# coreboards_mod001_rp2040_v01.net
KiCad netlist of a schematic drawn in EasyEDA Pro
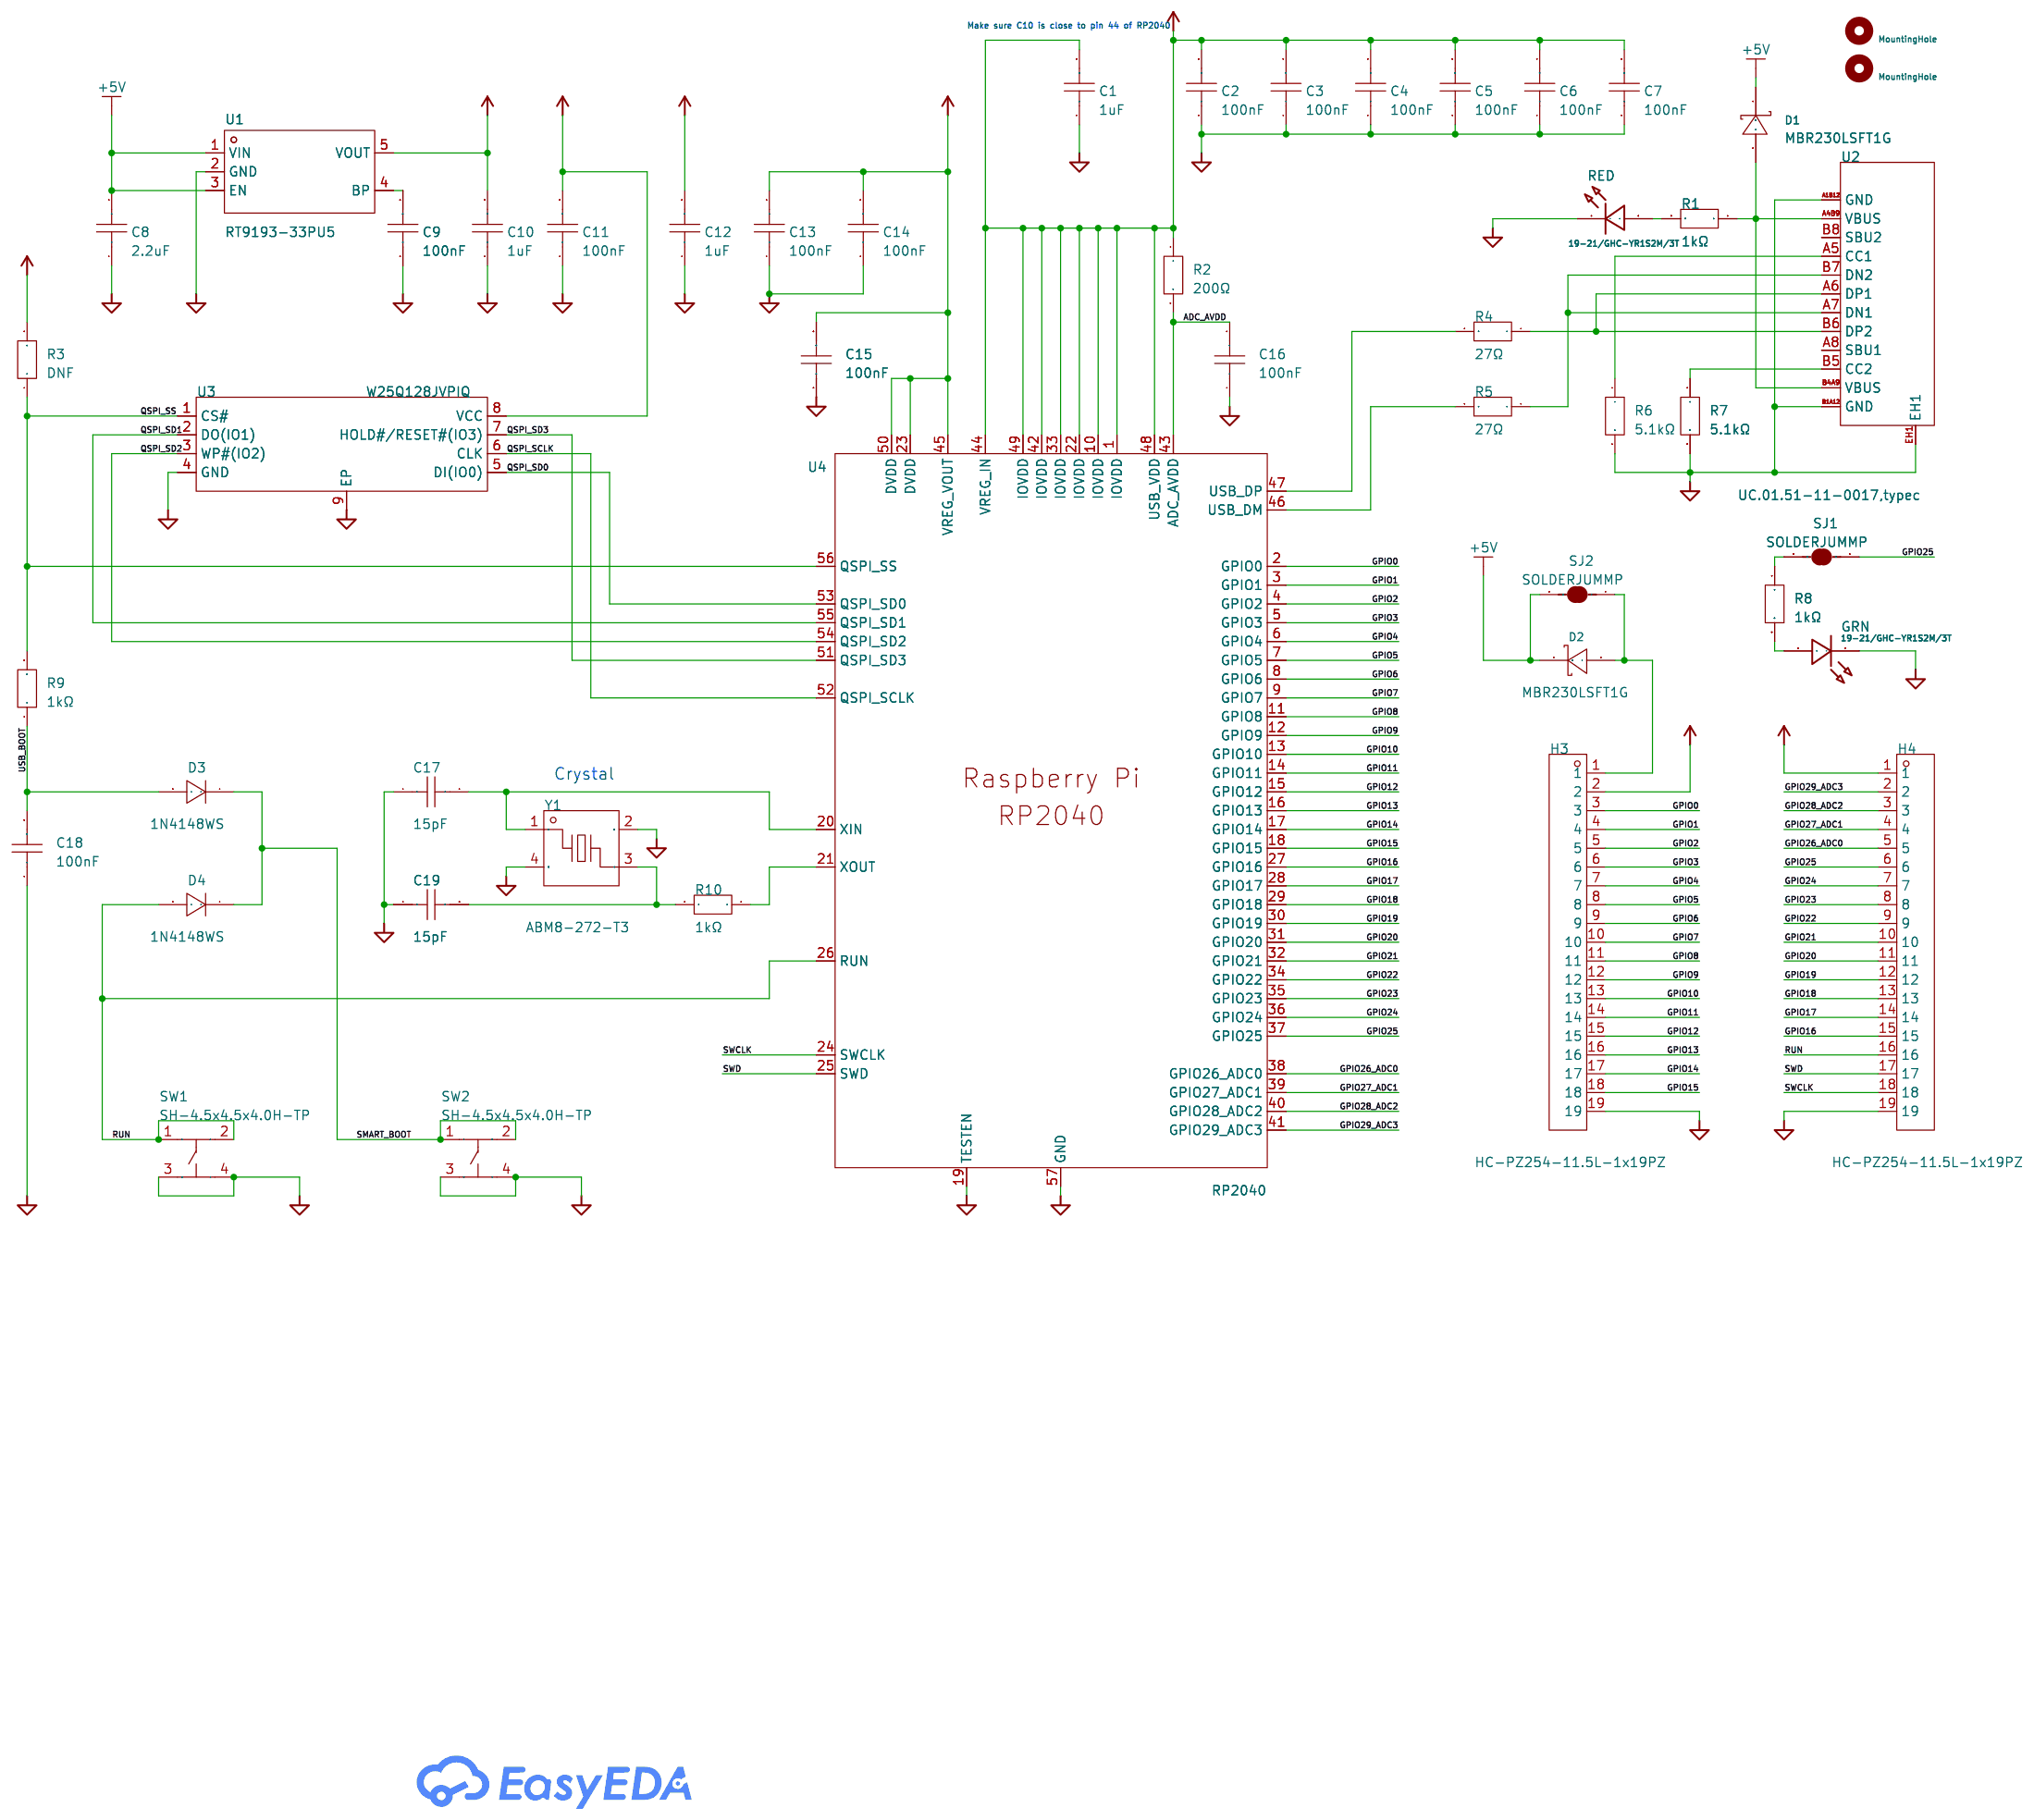
[diagram p0: schematic sheet]

(export (version "E")
  (design (tool "Eeschema 10.0.6"))
  (components
    (comp (ref "C1")
      (value "1uF")
      (footprint "easyedapro:C0603")
      (description "Capacitance:1nF Tolerance:±5% Tolerance:±5% Voltage Rating:200V Temperature Coefficient:C0G")
      (fields
        (field (name "Manufacturer Part") "C0603C102J2GECAUTO")
        (field (name "Manufacturer") "KEMET(基美)")
      )
      (libsource (lib "easyedapro") (part "C0603C102J2GECAUTO"))
    )
    (comp (ref "C2")
      (value "100nF")
      (footprint "easyedapro:C0603")
      (description "Capacitance:1nF Tolerance:±5% Tolerance:±5% Voltage Rating:200V Temperature Coefficient:C0G")
      (fields
        (field (name "Manufacturer Part") "C0603C102J2GECAUTO")
        (field (name "Manufacturer") "KEMET(基美)")
      )
      (libsource (lib "easyedapro") (part "C0603C102J2GECAUTO"))
    )
    (comp (ref "C3")
      (value "100nF")
      (footprint "easyedapro:C0603")
      (description "Capacitance:1nF Tolerance:±5% Tolerance:±5% Voltage Rating:200V Temperature Coefficient:C0G")
      (fields
        (field (name "Manufacturer Part") "C0603C102J2GECAUTO")
        (field (name "Manufacturer") "KEMET(基美)")
      )
      (libsource (lib "easyedapro") (part "C0603C102J2GECAUTO"))
    )
    (comp (ref "C4")
      (value "100nF")
      (footprint "easyedapro:C0603")
      (description "Capacitance:1nF Tolerance:±5% Tolerance:±5% Voltage Rating:200V Temperature Coefficient:C0G")
      (fields
        (field (name "Manufacturer Part") "C0603C102J2GECAUTO")
        (field (name "Manufacturer") "KEMET(基美)")
      )
      (libsource (lib "easyedapro") (part "C0603C102J2GECAUTO"))
    )
    (comp (ref "C5")
      (value "100nF")
      (footprint "easyedapro:C0603")
      (description "Capacitance:1nF Tolerance:±5% Tolerance:±5% Voltage Rating:200V Temperature Coefficient:C0G")
      (fields
        (field (name "Manufacturer Part") "C0603C102J2GECAUTO")
        (field (name "Manufacturer") "KEMET(基美)")
      )
      (libsource (lib "easyedapro") (part "C0603C102J2GECAUTO"))
    )
    (comp (ref "C6")
      (value "100nF")
      (footprint "easyedapro:C0603")
      (description "Capacitance:1nF Tolerance:±5% Tolerance:±5% Voltage Rating:200V Temperature Coefficient:C0G")
      (fields
        (field (name "Manufacturer Part") "C0603C102J2GECAUTO")
        (field (name "Manufacturer") "KEMET(基美)")
      )
      (libsource (lib "easyedapro") (part "C0603C102J2GECAUTO"))
    )
    (comp (ref "C7")
      (value "100nF")
      (footprint "easyedapro:C0603")
      (description "Capacitance:1nF Tolerance:±5% Tolerance:±5% Voltage Rating:200V Temperature Coefficient:C0G")
      (fields
        (field (name "Manufacturer Part") "C0603C102J2GECAUTO")
        (field (name "Manufacturer") "KEMET(基美)")
      )
      (libsource (lib "easyedapro") (part "C0603C102J2GECAUTO"))
    )
    (comp (ref "C8")
      (value "2.2uF")
      (footprint "easyedapro:C0603")
      (description "Capacitance:1nF Tolerance:±5% Tolerance:±5% Voltage Rating:200V Temperature Coefficient:C0G")
      (fields
        (field (name "Manufacturer Part") "C0603C102J2GECAUTO")
        (field (name "Manufacturer") "KEMET(基美)")
      )
      (libsource (lib "easyedapro") (part "C0603C102J2GECAUTO"))
    )
    (comp (ref "C9")
      (value "100nF")
      (footprint "easyedapro:C0603")
      (description "Capacitance:1nF Tolerance:±5% Tolerance:±5% Voltage Rating:200V Temperature Coefficient:C0G")
      (fields
        (field (name "Manufacturer Part") "C0603C102J2GECAUTO")
        (field (name "Manufacturer") "KEMET(基美)")
      )
      (libsource (lib "easyedapro") (part "C0603C102J2GECAUTO"))
    )
    (comp (ref "C10")
      (value "1uF")
      (footprint "easyedapro:C0603")
      (description "Capacitance:1nF Tolerance:±5% Tolerance:±5% Voltage Rating:200V Temperature Coefficient:C0G")
      (fields
        (field (name "Manufacturer Part") "C0603C102J2GECAUTO")
        (field (name "Manufacturer") "KEMET(基美)")
      )
      (libsource (lib "easyedapro") (part "C0603C102J2GECAUTO"))
    )
    (comp (ref "C11")
      (value "100nF")
      (footprint "easyedapro:C0603")
      (description "Capacitance:1nF Tolerance:±5% Tolerance:±5% Voltage Rating:200V Temperature Coefficient:C0G")
      (fields
        (field (name "Manufacturer Part") "C0603C102J2GECAUTO")
        (field (name "Manufacturer") "KEMET(基美)")
      )
      (libsource (lib "easyedapro") (part "C0603C102J2GECAUTO"))
    )
    (comp (ref "C12")
      (value "1uF")
      (footprint "easyedapro:C0603")
      (description "Capacitance:1nF Tolerance:±5% Tolerance:±5% Voltage Rating:200V Temperature Coefficient:C0G")
      (fields
        (field (name "Manufacturer Part") "C0603C102J2GECAUTO")
        (field (name "Manufacturer") "KEMET(基美)")
      )
      (libsource (lib "easyedapro") (part "C0603C102J2GECAUTO"))
    )
    (comp (ref "C13")
      (value "100nF")
      (footprint "easyedapro:C0603")
      (description "Capacitance:1nF Tolerance:±5% Tolerance:±5% Voltage Rating:200V Temperature Coefficient:C0G")
      (fields
        (field (name "Manufacturer Part") "C0603C102J2GECAUTO")
        (field (name "Manufacturer") "KEMET(基美)")
      )
      (libsource (lib "easyedapro") (part "C0603C102J2GECAUTO"))
    )
    (comp (ref "C14")
      (value "100nF")
      (footprint "easyedapro:C0603")
      (description "Capacitance:1nF Tolerance:±5% Tolerance:±5% Voltage Rating:200V Temperature Coefficient:C0G")
      (fields
        (field (name "Manufacturer Part") "C0603C102J2GECAUTO")
        (field (name "Manufacturer") "KEMET(基美)")
      )
      (libsource (lib "easyedapro") (part "C0603C102J2GECAUTO"))
    )
    (comp (ref "C15")
      (value "100nF")
      (footprint "easyedapro:C0603")
      (description "Capacitance:1nF Tolerance:±5% Tolerance:±5% Voltage Rating:200V Temperature Coefficient:C0G")
      (fields
        (field (name "Manufacturer Part") "C0603C102J2GECAUTO")
        (field (name "Manufacturer") "KEMET(基美)")
      )
      (libsource (lib "easyedapro") (part "C0603C102J2GECAUTO"))
    )
    (comp (ref "C16")
      (value "100nF")
      (footprint "easyedapro:C0603")
      (description "Capacitance:1nF Tolerance:±5% Tolerance:±5% Voltage Rating:200V Temperature Coefficient:C0G")
      (fields
        (field (name "Manufacturer Part") "C0603C102J2GECAUTO")
        (field (name "Manufacturer") "KEMET(基美)")
      )
      (libsource (lib "easyedapro") (part "C0603C102J2GECAUTO"))
    )
    (comp (ref "C17")
      (value "15pF")
      (footprint "easyedapro:C0603")
      (description "Capacitance:1nF Tolerance:±5% Tolerance:±5% Voltage Rating:200V Temperature Coefficient:C0G")
      (fields
        (field (name "Manufacturer Part") "C0603C102J2GECAUTO")
        (field (name "Manufacturer") "KEMET(基美)")
      )
      (libsource (lib "easyedapro") (part "C0603C102J2GECAUTO"))
    )
    (comp (ref "C18")
      (value "100nF")
      (footprint "easyedapro:C0603")
      (description "Capacitance:1nF Tolerance:±5% Tolerance:±5% Voltage Rating:200V Temperature Coefficient:C0G")
      (fields
        (field (name "Manufacturer Part") "C0603C102J2GECAUTO")
        (field (name "Manufacturer") "KEMET(基美)")
      )
      (libsource (lib "easyedapro") (part "C0603C102J2GECAUTO"))
    )
    (comp (ref "C19")
      (value "15pF")
      (footprint "easyedapro:C0603")
      (description "Capacitance:1nF Tolerance:±5% Tolerance:±5% Voltage Rating:200V Temperature Coefficient:C0G")
      (fields
        (field (name "Manufacturer Part") "C0603C102J2GECAUTO")
        (field (name "Manufacturer") "KEMET(基美)")
      )
      (libsource (lib "easyedapro") (part "C0603C102J2GECAUTO"))
    )
    (comp (ref "D1")
      (value "MBR230LSFT1G")
      (footprint "easyedapro:SOD-123FL_L2.7-W1.8-LS3.8-RD")
      (fields (field (name "Manufacturer") "onsemi(安森美)"))
      (libsource (lib "easyedapro") (part "MBR230LSFT1G"))
    )
    (comp (ref "D2")
      (value "MBR230LSFT1G")
      (footprint "easyedapro:SOD-123FL_L2.7-W1.8-LS3.8-RD")
      (fields (field (name "Manufacturer") "onsemi(安森美)"))
      (libsource (lib "easyedapro") (part "MBR230LSFT1G"))
    )
    (comp (ref "D3")
      (value "1N4148WS")
      (footprint "easyedapro:SOD-323_L1.8-W1.3-LS2.5-RD")
      (fields (field (name "Manufacturer") "CJ(江苏长电/长晶)"))
      (libsource (lib "easyedapro") (part "1N4148WS T4"))
    )
    (comp (ref "D4")
      (value "1N4148WS")
      (footprint "easyedapro:SOD-323_L1.8-W1.3-LS2.5-RD")
      (fields (field (name "Manufacturer") "CJ(江苏长电/长晶)"))
      (libsource (lib "easyedapro") (part "1N4148WS T4"))
    )
    (comp (ref "GRN")
      (value "19-21/GHC-YR1S2M/3T")
      (footprint "easyedapro:LED-SMD_L1.6-W0.8-RD")
      (fields (field (name "Manufacturer") "EVERLIGHT(亿光)") (field (name "Contributor") "LCSC"))
      (libsource (lib "easyedapro") (part "19-21/GHC-YR1S2M/3T"))
    )
    (comp (ref "H1")
      (value "MountingHole")
      (footprint "easyedapro:MountingHole:MountingHole_2.7mm_M2.5")
      (libsource (lib "easyedapro") (part "Mechanical_MountingHole"))
    )
    (comp (ref "H2")
      (value "MountingHole")
      (footprint "easyedapro:MountingHole:MountingHole_2.7mm_M2.5")
      (libsource (lib "easyedapro") (part "Mechanical_MountingHole"))
    )
    (comp (ref "H3")
      (value "HC-PZ254-11.5L-1x19PZ")
      (footprint "easyedapro:HDR-TH_19P-P2.54-V-M")
      (fields (field (name "Manufacturer") "HC(虹成电子)"))
      (libsource (lib "easyedapro") (part "HC-PZ254-11.5L-1X19PZ"))
    )
    (comp (ref "H4")
      (value "HC-PZ254-11.5L-1x19PZ")
      (footprint "easyedapro:HDR-TH_19P-P2.54-V-M")
      (fields (field (name "Manufacturer") "HC(虹成电子)"))
      (libsource (lib "easyedapro") (part "HC-PZ254-11.5L-1X19PZ"))
    )
    (comp (ref "R1")
      (value "1kΩ")
      (footprint "easyedapro:R0603")
      (fields (field (name "Manufacturer Part") "RCC06031K50FKEA") (field (name "Manufacturer") "VISHAY(威世)"))
      (libsource (lib "easyedapro") (part "RCC06031K50FKEA"))
    )
    (comp (ref "R2")
      (value "200Ω")
      (footprint "easyedapro:R0603")
      (fields (field (name "Manufacturer Part") "RCC06031K50FKEA") (field (name "Manufacturer") "VISHAY(威世)"))
      (libsource (lib "easyedapro") (part "RCC06031K50FKEA"))
    )
    (comp (ref "R3")
      (value "DNF")
      (footprint "easyedapro:R0603")
      (fields (field (name "Manufacturer Part") "RCC06031K50FKEA") (field (name "Manufacturer") "VISHAY(威世)"))
      (libsource (lib "easyedapro") (part "RCC06031K50FKEA"))
    )
    (comp (ref "R4")
      (value "27Ω")
      (footprint "easyedapro:R0603")
      (fields (field (name "Manufacturer Part") "RCC06031K50FKEA") (field (name "Manufacturer") "VISHAY(威世)"))
      (libsource (lib "easyedapro") (part "RCC06031K50FKEA"))
    )
    (comp (ref "R5")
      (value "27Ω")
      (footprint "easyedapro:R0603")
      (fields (field (name "Manufacturer Part") "RCC06031K50FKEA") (field (name "Manufacturer") "VISHAY(威世)"))
      (libsource (lib "easyedapro") (part "RCC06031K50FKEA"))
    )
    (comp (ref "R6")
      (value "5.1kΩ")
      (footprint "easyedapro:R0603")
      (fields (field (name "Manufacturer Part") "RCC06031K50FKEA") (field (name "Manufacturer") "VISHAY(威世)"))
      (libsource (lib "easyedapro") (part "RCC06031K50FKEA"))
    )
    (comp (ref "R7")
      (value "5.1kΩ")
      (footprint "easyedapro:R0603")
      (fields (field (name "Manufacturer Part") "RCC06031K50FKEA") (field (name "Manufacturer") "VISHAY(威世)"))
      (libsource (lib "easyedapro") (part "RCC06031K50FKEA"))
    )
    (comp (ref "R8")
      (value "1kΩ")
      (footprint "easyedapro:R0603")
      (fields (field (name "Manufacturer Part") "RCC06031K50FKEA") (field (name "Manufacturer") "VISHAY(威世)"))
      (libsource (lib "easyedapro") (part "RCC06031K50FKEA"))
    )
    (comp (ref "R9")
      (value "1kΩ")
      (footprint "easyedapro:R0603")
      (fields (field (name "Manufacturer Part") "RCC06031K50FKEA") (field (name "Manufacturer") "VISHAY(威世)"))
      (libsource (lib "easyedapro") (part "RCC06031K50FKEA"))
    )
    (comp (ref "R10")
      (value "1kΩ")
      (footprint "easyedapro:R0603")
      (fields (field (name "Manufacturer Part") "RCC06031K50FKEA") (field (name "Manufacturer") "VISHAY(威世)"))
      (libsource (lib "easyedapro") (part "RCC06031K50FKEA"))
    )
    (comp (ref "RED")
      (value "19-21/GHC-YR1S2M/3T")
      (footprint "easyedapro:LED-SMD_L1.6-W0.8-RD")
      (fields (field (name "Manufacturer") "EVERLIGHT(亿光)") (field (name "Contributor") "LCSC"))
      (libsource (lib "easyedapro") (part "19-21/GHC-YR1S2M/3T"))
    )
    (comp (ref "SJ1")
      (value "SOLDERJUMMP")
      (footprint "easyedapro:SJ_2S-NO")
      (fields (field (name "Contributor") "SparkFun"))
      (libsource (lib "easyedapro") (part "SOLDERJUMPERNO"))
    )
    (comp (ref "SJ2")
      (value "SOLDERJUMMP")
      (footprint "easyedapro:SJ_2S-NO")
      (fields (field (name "Contributor") "SparkFun"))
      (libsource (lib "easyedapro") (part "SOLDERJUMPERNO"))
    )
    (comp (ref "SW1")
      (value "SH-4.5x4.5x4.0H-TP")
      (footprint "easyedapro:SW-SMD_4P-SH-4.5X4.5X4.0H-TP")
      (fields (field (name "Manufacturer") "SHOU HAN(首韩)"))
      (libsource (lib "easyedapro") (part "SH-4.5X4.5X4.0H-TP"))
    )
    (comp (ref "SW2")
      (value "SH-4.5x4.5x4.0H-TP")
      (footprint "easyedapro:SW-SMD_4P-SH-4.5X4.5X4.0H-TP")
      (fields (field (name "Manufacturer") "SHOU HAN(首韩)"))
      (libsource (lib "easyedapro") (part "SH-4.5X4.5X4.0H-TP"))
    )
    (comp (ref "U1")
      (value "RT9193-33PU5")
      (footprint "easyedapro:SC-70-5_L2.0-W1.3-P0.65-LS2.1-BL")
      (description "Output Type:-")
      (libsource (lib "easyedapro") (part "RT9193-33PU5"))
    )
    (comp (ref "U2")
      (value "UC.01.51-11-0017,typec")
      (footprint "easyedapro:TYPE-C-SMD_UC.01.51-11-0017")
      (libsource (lib "easyedapro") (part "UC.01.51-11-0017,TYPEC"))
    )
    (comp (ref "U3")
      (value "W25Q128JVPIQ")
      (footprint "easyedapro:WSON-8_L5.0-W6.0-P1.27-BL-EP")
      (fields (field (name "Manufacturer") "Winbond(华邦)"))
      (libsource (lib "easyedapro") (part "W25Q128JVPIQ"))
    )
    (comp (ref "U4")
      (value "RP2040")
      (footprint "easyedapro:QFN-56_L7.0-W7.0-P0.40-TL-EP4.0")
      (fields (field (name "Manufacturer") "Raspberry Pi(树莓派)"))
      (libsource (lib "easyedapro") (part "RP2040_C2961140"))
    )
    (comp (ref "Y1")
      (value "ABM8-272-T3")
      (footprint "easyedapro:CRYSTAL-SMD_4P-L3.2-W2.5-BL-2")
      (libsource (lib "easyedapro") (part "ABM8-272-T3"))
    )
  )
  (nets
    (net (code "1") (name "+5V") (class "Default")
      (node (ref "C8") (pin "2") (pinfunction "2_2") (pintype "unspecified"))
      (node (ref "D1") (pin "1") (pinfunction "C_1") (pintype "input"))
      (node (ref "D2") (pin "1") (pinfunction "C_1") (pintype "input"))
      (node (ref "SJ2") (pin "2") (pinfunction "2_2") (pintype "unspecified"))
      (node (ref "U1") (pin "1") (pinfunction "VIN_1") (pintype "unspecified"))
      (node (ref "U1") (pin "3") (pinfunction "EN_3") (pintype "unspecified"))
    )
    (net (code "2") (name "/ADC_AVDD") (class "Default")
      (node (ref "C16") (pin "2") (pinfunction "2_2") (pintype "unspecified"))
      (node (ref "R2") (pin "2") (pinfunction "2_2") (pintype "unspecified"))
      (node (ref "U4") (pin "43") (pinfunction "ADC_AVDD_43") (pintype "bidirectional"))
    )
    (net (code "3") (name "/GPIO0") (class "Default")
      (node (ref "H3") (pin "3") (pinfunction "3_3") (pintype "unspecified"))
      (node (ref "U4") (pin "2") (pinfunction "GPIO0_2") (pintype "bidirectional"))
    )
    (net (code "4") (name "/GPIO1") (class "Default")
      (node (ref "H3") (pin "4") (pinfunction "4_4") (pintype "unspecified"))
      (node (ref "U4") (pin "3") (pinfunction "GPIO1_3") (pintype "bidirectional"))
    )
    (net (code "5") (name "/GPIO2") (class "Default")
      (node (ref "H3") (pin "5") (pinfunction "5_5") (pintype "unspecified"))
      (node (ref "U4") (pin "4") (pinfunction "GPIO2_4") (pintype "bidirectional"))
    )
    (net (code "6") (name "/GPIO3") (class "Default")
      (node (ref "H3") (pin "6") (pinfunction "6_6") (pintype "unspecified"))
      (node (ref "U4") (pin "5") (pinfunction "GPIO3_5") (pintype "bidirectional"))
    )
    (net (code "7") (name "/GPIO4") (class "Default")
      (node (ref "H3") (pin "7") (pinfunction "7_7") (pintype "unspecified"))
      (node (ref "U4") (pin "6") (pinfunction "GPIO4_6") (pintype "bidirectional"))
    )
    (net (code "8") (name "/GPIO5") (class "Default")
      (node (ref "H3") (pin "8") (pinfunction "8_8") (pintype "unspecified"))
      (node (ref "U4") (pin "7") (pinfunction "GPIO5_7") (pintype "bidirectional"))
    )
    (net (code "9") (name "/GPIO6") (class "Default")
      (node (ref "H3") (pin "9") (pinfunction "9_9") (pintype "unspecified"))
      (node (ref "U4") (pin "8") (pinfunction "GPIO6_8") (pintype "bidirectional"))
    )
    (net (code "10") (name "/GPIO7") (class "Default")
      (node (ref "H3") (pin "10") (pinfunction "10_10") (pintype "unspecified"))
      (node (ref "U4") (pin "9") (pinfunction "GPIO7_9") (pintype "bidirectional"))
    )
    (net (code "11") (name "/GPIO8") (class "Default")
      (node (ref "H3") (pin "11") (pinfunction "11_11") (pintype "unspecified"))
      (node (ref "U4") (pin "11") (pinfunction "GPIO8_11") (pintype "bidirectional"))
    )
    (net (code "12") (name "/GPIO9") (class "Default")
      (node (ref "H3") (pin "12") (pinfunction "12_12") (pintype "unspecified"))
      (node (ref "U4") (pin "12") (pinfunction "GPIO9_12") (pintype "bidirectional"))
    )
    (net (code "13") (name "/GPIO10") (class "Default")
      (node (ref "H3") (pin "13") (pinfunction "13_13") (pintype "unspecified"))
      (node (ref "U4") (pin "13") (pinfunction "GPIO10_13") (pintype "bidirectional"))
    )
    (net (code "14") (name "/GPIO11") (class "Default")
      (node (ref "H3") (pin "14") (pinfunction "14_14") (pintype "unspecified"))
      (node (ref "U4") (pin "14") (pinfunction "GPIO11_14") (pintype "bidirectional"))
    )
    (net (code "15") (name "/GPIO12") (class "Default")
      (node (ref "H3") (pin "15") (pinfunction "15_15") (pintype "unspecified"))
      (node (ref "U4") (pin "15") (pinfunction "GPIO12_15") (pintype "bidirectional"))
    )
    (net (code "16") (name "/GPIO13") (class "Default")
      (node (ref "H3") (pin "16") (pinfunction "16_16") (pintype "unspecified"))
      (node (ref "U4") (pin "16") (pinfunction "GPIO13_16") (pintype "bidirectional"))
    )
    (net (code "17") (name "/GPIO14") (class "Default")
      (node (ref "H3") (pin "17") (pinfunction "17_17") (pintype "unspecified"))
      (node (ref "U4") (pin "17") (pinfunction "GPIO14_17") (pintype "bidirectional"))
    )
    (net (code "18") (name "/GPIO15") (class "Default")
      (node (ref "H3") (pin "18") (pinfunction "18_18") (pintype "unspecified"))
      (node (ref "U4") (pin "18") (pinfunction "GPIO15_18") (pintype "bidirectional"))
    )
    (net (code "19") (name "/GPIO16") (class "Default")
      (node (ref "H4") (pin "15") (pinfunction "15_15") (pintype "unspecified"))
      (node (ref "U4") (pin "27") (pinfunction "GPIO16_27") (pintype "bidirectional"))
    )
    (net (code "20") (name "/GPIO17") (class "Default")
      (node (ref "H4") (pin "14") (pinfunction "14_14") (pintype "unspecified"))
      (node (ref "U4") (pin "28") (pinfunction "GPIO17_28") (pintype "bidirectional"))
    )
    (net (code "21") (name "/GPIO18") (class "Default")
      (node (ref "H4") (pin "13") (pinfunction "13_13") (pintype "unspecified"))
      (node (ref "U4") (pin "29") (pinfunction "GPIO18_29") (pintype "bidirectional"))
    )
    (net (code "22") (name "/GPIO19") (class "Default")
      (node (ref "H4") (pin "12") (pinfunction "12_12") (pintype "unspecified"))
      (node (ref "U4") (pin "30") (pinfunction "GPIO19_30") (pintype "bidirectional"))
    )
    (net (code "23") (name "/GPIO20") (class "Default")
      (node (ref "H4") (pin "11") (pinfunction "11_11") (pintype "unspecified"))
      (node (ref "U4") (pin "31") (pinfunction "GPIO20_31") (pintype "bidirectional"))
    )
    (net (code "24") (name "/GPIO21") (class "Default")
      (node (ref "H4") (pin "10") (pinfunction "10_10") (pintype "unspecified"))
      (node (ref "U4") (pin "32") (pinfunction "GPIO21_32") (pintype "bidirectional"))
    )
    (net (code "25") (name "/GPIO22") (class "Default")
      (node (ref "H4") (pin "9") (pinfunction "9_9") (pintype "unspecified"))
      (node (ref "U4") (pin "34") (pinfunction "GPIO22_34") (pintype "bidirectional"))
    )
    (net (code "26") (name "/GPIO23") (class "Default")
      (node (ref "H4") (pin "8") (pinfunction "8_8") (pintype "unspecified"))
      (node (ref "U4") (pin "35") (pinfunction "GPIO23_35") (pintype "bidirectional"))
    )
    (net (code "27") (name "/GPIO24") (class "Default")
      (node (ref "H4") (pin "7") (pinfunction "7_7") (pintype "unspecified"))
      (node (ref "U4") (pin "36") (pinfunction "GPIO24_36") (pintype "bidirectional"))
    )
    (net (code "28") (name "/GPIO25") (class "Default")
      (node (ref "H4") (pin "6") (pinfunction "6_6") (pintype "unspecified"))
      (node (ref "SJ1") (pin "1") (pinfunction "1_1") (pintype "unspecified"))
      (node (ref "U4") (pin "37") (pinfunction "GPIO25_37") (pintype "bidirectional"))
    )
    (net (code "29") (name "/GPIO26_ADC0") (class "Default")
      (node (ref "H4") (pin "5") (pinfunction "5_5") (pintype "unspecified"))
      (node (ref "U4") (pin "38") (pinfunction "GPIO26_ADC0_38") (pintype "bidirectional"))
    )
    (net (code "30") (name "/GPIO27_ADC1") (class "Default")
      (node (ref "H4") (pin "4") (pinfunction "4_4") (pintype "unspecified"))
      (node (ref "U4") (pin "39") (pinfunction "GPIO27_ADC1_39") (pintype "bidirectional"))
    )
    (net (code "31") (name "/GPIO28_ADC2") (class "Default")
      (node (ref "H4") (pin "3") (pinfunction "3_3") (pintype "unspecified"))
      (node (ref "U4") (pin "40") (pinfunction "GPIO28_ADC2_40") (pintype "bidirectional"))
    )
    (net (code "32") (name "/GPIO29_ADC3") (class "Default")
      (node (ref "H4") (pin "2") (pinfunction "2_2") (pintype "unspecified"))
      (node (ref "U4") (pin "41") (pinfunction "GPIO29_ADC3_41") (pintype "bidirectional"))
    )
    (net (code "33") (name "/QSPI_SCLK") (class "Default")
      (node (ref "U3") (pin "6") (pinfunction "CLK_6") (pintype "unspecified"))
      (node (ref "U4") (pin "52") (pinfunction "QSPI_SCLK_52") (pintype "output"))
    )
    (net (code "34") (name "/QSPI_SD0") (class "Default")
      (node (ref "U3") (pin "5") (pinfunction "DI(IO0)_5") (pintype "unspecified"))
      (node (ref "U4") (pin "53") (pinfunction "QSPI_SD0_53") (pintype "bidirectional"))
    )
    (net (code "35") (name "/QSPI_SD1") (class "Default")
      (node (ref "U3") (pin "2") (pinfunction "DO(IO1)_2") (pintype "unspecified"))
      (node (ref "U4") (pin "55") (pinfunction "QSPI_SD1_55") (pintype "bidirectional"))
    )
    (net (code "36") (name "/QSPI_SD2") (class "Default")
      (node (ref "U3") (pin "3") (pinfunction "WP#(IO2)_3") (pintype "unspecified"))
      (node (ref "U4") (pin "54") (pinfunction "QSPI_SD2_54") (pintype "bidirectional"))
    )
    (net (code "37") (name "/QSPI_SD3") (class "Default")
      (node (ref "U3") (pin "7") (pinfunction "HOLD#/RESET#(IO3)_7") (pintype "unspecified"))
      (node (ref "U4") (pin "51") (pinfunction "QSPI_SD3_51") (pintype "bidirectional"))
    )
    (net (code "38") (name "/QSPI_SS") (class "Default")
      (node (ref "R3") (pin "1") (pinfunction "1_1") (pintype "unspecified"))
      (node (ref "R9") (pin "2") (pinfunction "2_2") (pintype "unspecified"))
      (node (ref "U3") (pin "1") (pinfunction "CS#_1") (pintype "unspecified"))
      (node (ref "U4") (pin "56") (pinfunction "QSPI_SS_56") (pintype "bidirectional"))
    )
    (net (code "39") (name "/RUN") (class "Default")
      (node (ref "D4") (pin "2") (pinfunction "A_2") (pintype "unspecified"))
      (node (ref "H4") (pin "16") (pinfunction "16_16") (pintype "unspecified"))
      (node (ref "SW1") (pin "1") (pinfunction "1_1") (pintype "unspecified"))
      (node (ref "SW1") (pin "2") (pinfunction "2_2") (pintype "unspecified"))
      (node (ref "U4") (pin "26") (pinfunction "RUN_26") (pintype "input"))
    )
    (net (code "40") (name "/SMART_BOOT") (class "Default")
      (node (ref "D3") (pin "1") (pinfunction "K_1") (pintype "unspecified"))
      (node (ref "D4") (pin "1") (pinfunction "K_1") (pintype "unspecified"))
      (node (ref "SW2") (pin "1") (pinfunction "1_1") (pintype "unspecified"))
      (node (ref "SW2") (pin "2") (pinfunction "2_2") (pintype "unspecified"))
    )
    (net (code "41") (name "/SWCLK") (class "Default")
      (node (ref "H4") (pin "18") (pinfunction "18_18") (pintype "unspecified"))
      (node (ref "U4") (pin "24") (pinfunction "SWCLK_24") (pintype "output"))
    )
    (net (code "42") (name "/SWD") (class "Default")
      (node (ref "H4") (pin "17") (pinfunction "17_17") (pintype "unspecified"))
      (node (ref "U4") (pin "25") (pinfunction "SWD_25") (pintype "bidirectional"))
    )
    (net (code "43") (name "/USB_BOOT") (class "Default")
      (node (ref "C18") (pin "2") (pinfunction "2_2") (pintype "unspecified"))
      (node (ref "D3") (pin "2") (pinfunction "A_2") (pintype "unspecified"))
      (node (ref "R9") (pin "1") (pinfunction "1_1") (pintype "unspecified"))
    )
    (net (code "44") (name "Net-(C19-Pad2)") (class "Default")
      (node (ref "C19") (pin "2") (pinfunction "2_2") (pintype "unspecified"))
      (node (ref "R10") (pin "2") (pinfunction "2_2") (pintype "unspecified"))
      (node (ref "Y1") (pin "3") (pinfunction "3_3") (pintype "input"))
    )
    (net (code "45") (name "Net-(D1-A)") (class "Default")
      (node (ref "D1") (pin "2") (pinfunction "A_2") (pintype "input"))
      (node (ref "R1") (pin "1") (pinfunction "1_1") (pintype "unspecified"))
      (node (ref "U2") (pin "A4B9") (pinfunction "VBUS_A4B9") (pintype "unspecified"))
      (node (ref "U2") (pin "B4A9") (pinfunction "VBUS_B4A9") (pintype "unspecified"))
    )
    (net (code "46") (name "Net-(D2-A)") (class "Default")
      (node (ref "D2") (pin "2") (pinfunction "A_2") (pintype "input"))
      (node (ref "H3") (pin "1") (pinfunction "1_1") (pintype "unspecified"))
      (node (ref "SJ2") (pin "1") (pinfunction "1_1") (pintype "unspecified"))
    )
    (net (code "47") (name "Net-(GRN-+)") (class "Default")
      (node (ref "GRN") (pin "2") (pinfunction "+_2") (pintype "unspecified"))
      (node (ref "R8") (pin "2") (pinfunction "2_2") (pintype "unspecified"))
    )
    (net (code "48") (name "Net-(R8-Pad1)") (class "Default")
      (node (ref "R8") (pin "1") (pinfunction "1_1") (pintype "unspecified"))
      (node (ref "SJ1") (pin "2") (pinfunction "2_2") (pintype "unspecified"))
    )
    (net (code "49") (name "Net-(RED-+)") (class "Default")
      (node (ref "R1") (pin "2") (pinfunction "2_2") (pintype "unspecified"))
      (node (ref "RED") (pin "2") (pinfunction "+_2") (pintype "unspecified"))
    )
    (net (code "50") (name "Net-(U1-BP)") (class "Default")
      (node (ref "C9") (pin "2") (pinfunction "2_2") (pintype "unspecified"))
      (node (ref "U1") (pin "4") (pinfunction "BP_4") (pintype "unspecified"))
    )
    (net (code "51") (name "Net-(U2-CC1)") (class "Default")
      (node (ref "R6") (pin "1") (pinfunction "1_1") (pintype "unspecified"))
      (node (ref "U2") (pin "A5") (pinfunction "CC1_A5") (pintype "unspecified"))
    )
    (net (code "52") (name "Net-(U2-CC2)") (class "Default")
      (node (ref "R7") (pin "1") (pinfunction "1_1") (pintype "unspecified"))
      (node (ref "U2") (pin "B5") (pinfunction "CC2_B5") (pintype "unspecified"))
    )
    (net (code "53") (name "Net-(U2-DN1)") (class "Default")
      (node (ref "R5") (pin "1") (pinfunction "1_1") (pintype "unspecified"))
      (node (ref "U2") (pin "A7") (pinfunction "DN1_A7") (pintype "unspecified"))
      (node (ref "U2") (pin "B7") (pinfunction "DN2_B7") (pintype "unspecified"))
    )
    (net (code "54") (name "Net-(U2-DP1)") (class "Default")
      (node (ref "R4") (pin "1") (pinfunction "1_1") (pintype "unspecified"))
      (node (ref "U2") (pin "A6") (pinfunction "DP1_A6") (pintype "unspecified"))
      (node (ref "U2") (pin "B6") (pinfunction "DP2_B6") (pintype "unspecified"))
    )
    (net (code "55") (name "Net-(U4-USB_DM)") (class "Default")
      (node (ref "R5") (pin "2") (pinfunction "2_2") (pintype "unspecified"))
      (node (ref "U4") (pin "46") (pinfunction "USB_DM_46") (pintype "bidirectional"))
    )
    (net (code "56") (name "Net-(U4-USB_DP)") (class "Default")
      (node (ref "R4") (pin "2") (pinfunction "2_2") (pintype "unspecified"))
      (node (ref "U4") (pin "47") (pinfunction "USB_DP_47") (pintype "bidirectional"))
    )
    (net (code "57") (name "Net-(U4-XIN)") (class "Default")
      (node (ref "C17") (pin "2") (pinfunction "2_2") (pintype "unspecified"))
      (node (ref "U4") (pin "20") (pinfunction "XIN_20") (pintype "input"))
      (node (ref "Y1") (pin "1") (pinfunction "1_1") (pintype "input"))
    )
    (net (code "58") (name "Net-(U4-XOUT)") (class "Default")
      (node (ref "R10") (pin "1") (pinfunction "1_1") (pintype "unspecified"))
      (node (ref "U4") (pin "21") (pinfunction "XOUT_21") (pintype "unspecified"))
    )
    (net (code "59") (name "POWER_+1V1") (class "Default")
      (node (ref "C13") (pin "2") (pinfunction "2_2") (pintype "unspecified"))
      (node (ref "C14") (pin "2") (pinfunction "2_2") (pintype "unspecified"))
      (node (ref "C15") (pin "2") (pinfunction "2_2") (pintype "unspecified"))
      (node (ref "U4") (pin "23") (pinfunction "DVDD_23") (pintype "bidirectional"))
      (node (ref "U4") (pin "45") (pinfunction "VREG_VOUT_45") (pintype "bidirectional"))
      (node (ref "U4") (pin "50") (pinfunction "DVDD_50") (pintype "bidirectional"))
    )
    (net (code "60") (name "POWER_+3V3") (class "Default")
      (node (ref "C1") (pin "2") (pinfunction "2_2") (pintype "unspecified"))
      (node (ref "C10") (pin "2") (pinfunction "2_2") (pintype "unspecified"))
      (node (ref "C11") (pin "2") (pinfunction "2_2") (pintype "unspecified"))
      (node (ref "C12") (pin "2") (pinfunction "2_2") (pintype "unspecified"))
      (node (ref "C2") (pin "2") (pinfunction "2_2") (pintype "unspecified"))
      (node (ref "C3") (pin "2") (pinfunction "2_2") (pintype "unspecified"))
      (node (ref "C4") (pin "2") (pinfunction "2_2") (pintype "unspecified"))
      (node (ref "C5") (pin "2") (pinfunction "2_2") (pintype "unspecified"))
      (node (ref "C6") (pin "2") (pinfunction "2_2") (pintype "unspecified"))
      (node (ref "C7") (pin "2") (pinfunction "2_2") (pintype "unspecified"))
      (node (ref "H3") (pin "2") (pinfunction "2_2") (pintype "unspecified"))
      (node (ref "H4") (pin "1") (pinfunction "1_1") (pintype "unspecified"))
      (node (ref "R2") (pin "1") (pinfunction "1_1") (pintype "unspecified"))
      (node (ref "R3") (pin "2") (pinfunction "2_2") (pintype "unspecified"))
      (node (ref "U1") (pin "5") (pinfunction "VOUT_5") (pintype "unspecified"))
      (node (ref "U3") (pin "8") (pinfunction "VCC_8") (pintype "unspecified"))
      (node (ref "U4") (pin "1") (pinfunction "IOVDD_1") (pintype "bidirectional"))
      (node (ref "U4") (pin "10") (pinfunction "IOVDD_10") (pintype "bidirectional"))
      (node (ref "U4") (pin "22") (pinfunction "IOVDD_22") (pintype "bidirectional"))
      (node (ref "U4") (pin "33") (pinfunction "IOVDD_33") (pintype "bidirectional"))
      (node (ref "U4") (pin "42") (pinfunction "IOVDD_42") (pintype "bidirectional"))
      (node (ref "U4") (pin "44") (pinfunction "VREG_IN_44") (pintype "bidirectional"))
      (node (ref "U4") (pin "48") (pinfunction "USB_VDD_48") (pintype "bidirectional"))
      (node (ref "U4") (pin "49") (pinfunction "IOVDD_49") (pintype "bidirectional"))
    )
    (net (code "61") (name "POWER_GND") (class "Default")
      (node (ref "C1") (pin "1") (pinfunction "1_1") (pintype "unspecified"))
      (node (ref "C10") (pin "1") (pinfunction "1_1") (pintype "unspecified"))
      (node (ref "C11") (pin "1") (pinfunction "1_1") (pintype "unspecified"))
      (node (ref "C12") (pin "1") (pinfunction "1_1") (pintype "unspecified"))
      (node (ref "C13") (pin "1") (pinfunction "1_1") (pintype "unspecified"))
      (node (ref "C14") (pin "1") (pinfunction "1_1") (pintype "unspecified"))
      (node (ref "C15") (pin "1") (pinfunction "1_1") (pintype "unspecified"))
      (node (ref "C16") (pin "1") (pinfunction "1_1") (pintype "unspecified"))
      (node (ref "C17") (pin "1") (pinfunction "1_1") (pintype "unspecified"))
      (node (ref "C18") (pin "1") (pinfunction "1_1") (pintype "unspecified"))
      (node (ref "C19") (pin "1") (pinfunction "1_1") (pintype "unspecified"))
      (node (ref "C2") (pin "1") (pinfunction "1_1") (pintype "unspecified"))
      (node (ref "C3") (pin "1") (pinfunction "1_1") (pintype "unspecified"))
      (node (ref "C4") (pin "1") (pinfunction "1_1") (pintype "unspecified"))
      (node (ref "C5") (pin "1") (pinfunction "1_1") (pintype "unspecified"))
      (node (ref "C6") (pin "1") (pinfunction "1_1") (pintype "unspecified"))
      (node (ref "C7") (pin "1") (pinfunction "1_1") (pintype "unspecified"))
      (node (ref "C8") (pin "1") (pinfunction "1_1") (pintype "unspecified"))
      (node (ref "C9") (pin "1") (pinfunction "1_1") (pintype "unspecified"))
      (node (ref "GRN") (pin "1") (pinfunction "-_1") (pintype "unspecified"))
      (node (ref "H3") (pin "19") (pinfunction "19_19") (pintype "unspecified"))
      (node (ref "H4") (pin "19") (pinfunction "19_19") (pintype "unspecified"))
      (node (ref "R6") (pin "2") (pinfunction "2_2") (pintype "unspecified"))
      (node (ref "R7") (pin "2") (pinfunction "2_2") (pintype "unspecified"))
      (node (ref "RED") (pin "1") (pinfunction "-_1") (pintype "unspecified"))
      (node (ref "SW1") (pin "3") (pinfunction "3_3") (pintype "unspecified"))
      (node (ref "SW1") (pin "4") (pinfunction "4_4") (pintype "unspecified"))
      (node (ref "SW2") (pin "3") (pinfunction "3_3") (pintype "unspecified"))
      (node (ref "SW2") (pin "4") (pinfunction "4_4") (pintype "unspecified"))
      (node (ref "U1") (pin "2") (pinfunction "GND_2") (pintype "unspecified"))
      (node (ref "U2") (pin "A1B12") (pinfunction "GND_A1B12") (pintype "unspecified"))
      (node (ref "U2") (pin "B1A12") (pinfunction "GND_B1A12") (pintype "unspecified"))
      (node (ref "U2") (pin "EH1") (pinfunction "EH1_EH1") (pintype "unspecified"))
      (node (ref "U3") (pin "4") (pinfunction "GND_4") (pintype "unspecified"))
      (node (ref "U3") (pin "9") (pinfunction "EP_9") (pintype "unspecified"))
      (node (ref "U4") (pin "19") (pinfunction "TESTEN_19") (pintype "unspecified"))
      (node (ref "U4") (pin "57") (pinfunction "GND_57") (pintype "bidirectional"))
      (node (ref "Y1") (pin "2") (pinfunction "GND_2") (pintype "input"))
      (node (ref "Y1") (pin "4") (pinfunction "GND_4") (pintype "input"))
    )
    (net (code "62") (name "unconnected-(U2-SBU1-PadA8)") (class "Default")
      (node (ref "U2") (pin "A8") (pinfunction "SBU1_A8") (pintype "unspecified"))
    )
    (net (code "63") (name "unconnected-(U2-SBU2-PadB8)") (class "Default")
      (node (ref "U2") (pin "B8") (pinfunction "SBU2_B8") (pintype "unspecified"))
    )
  )
)
